# multiplex.net
KiCad netlist of a schematic drawn in EAGLE
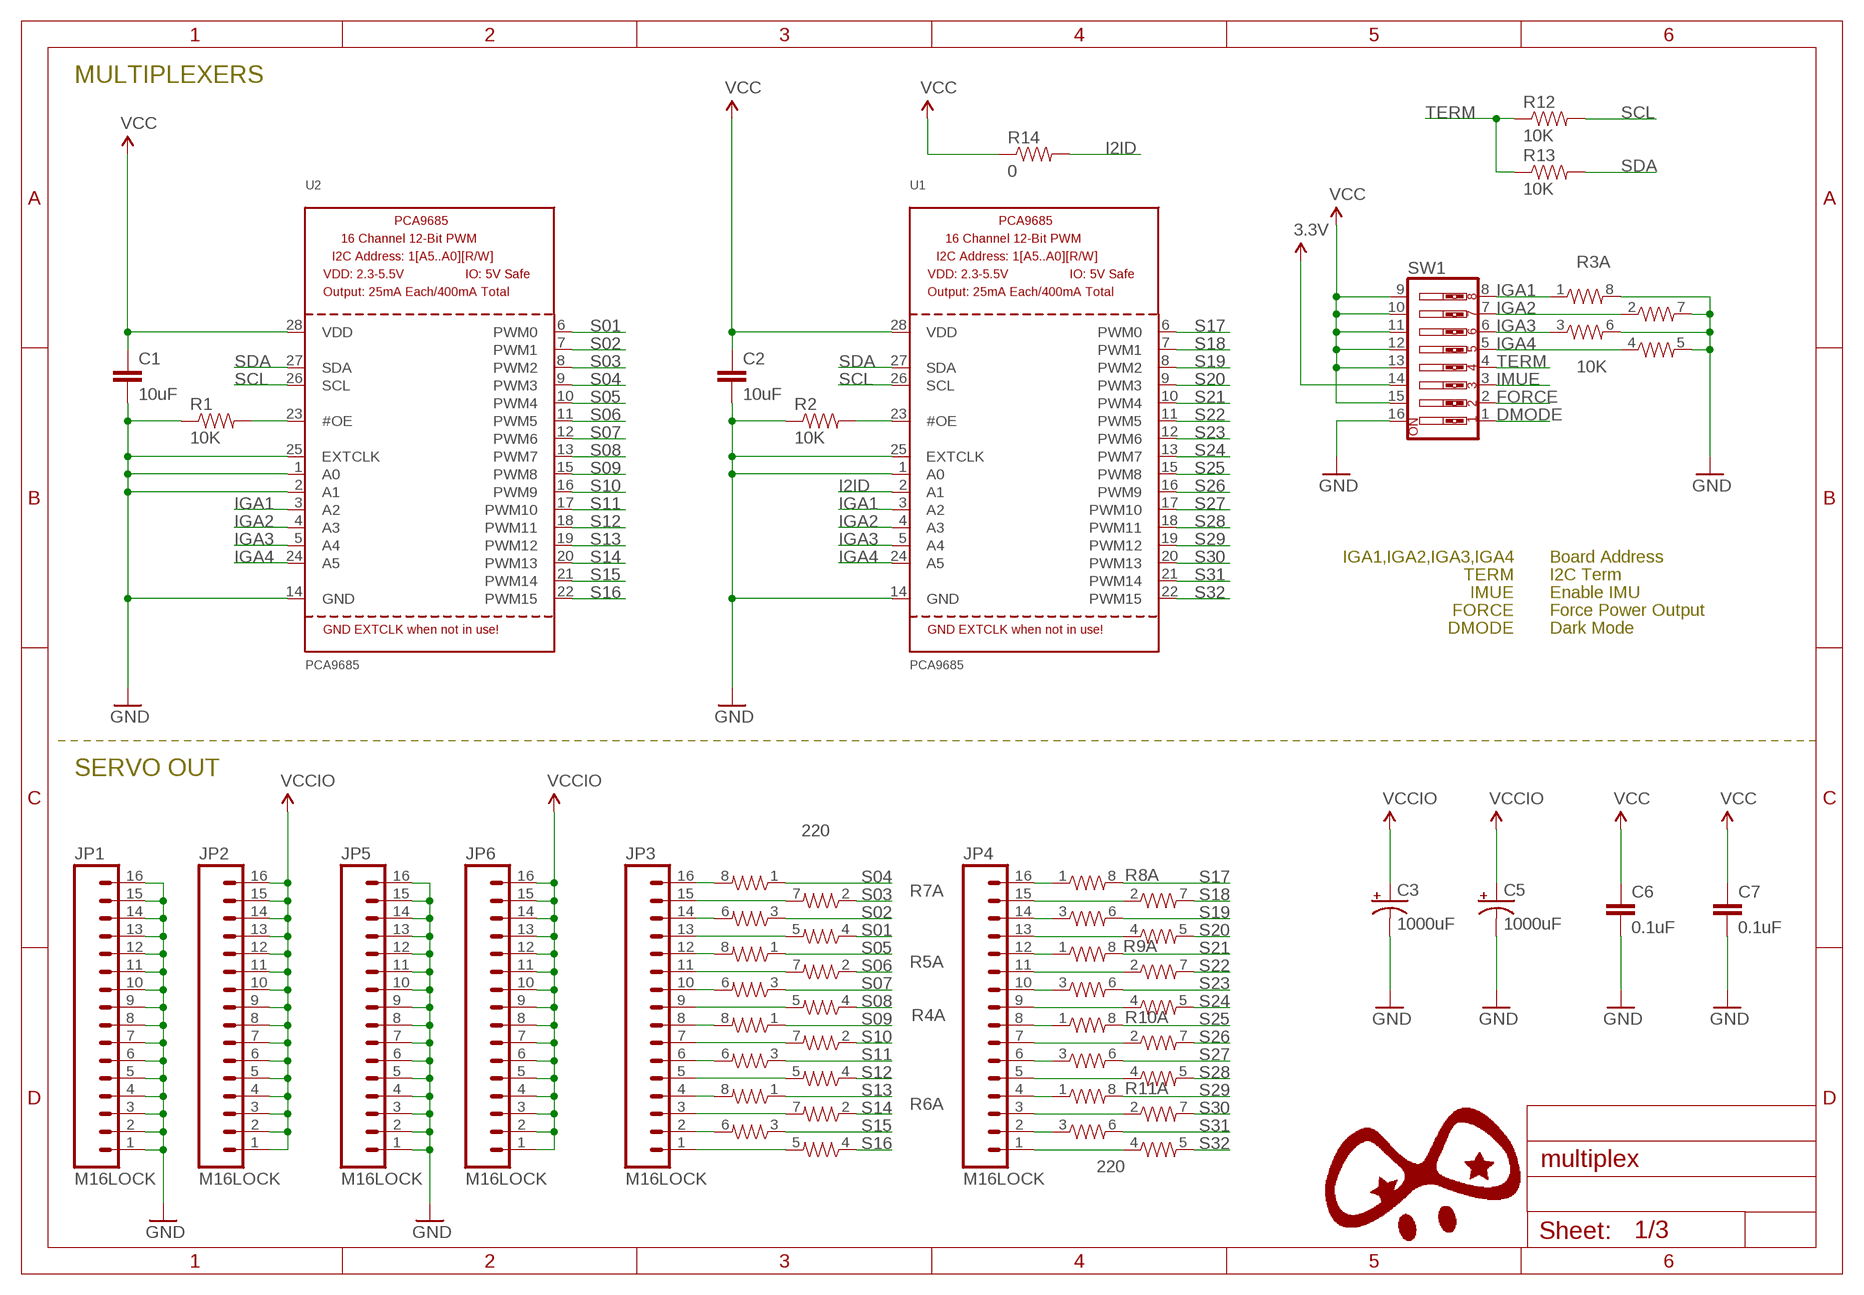
[diagram p0: schematic, sheet 1]
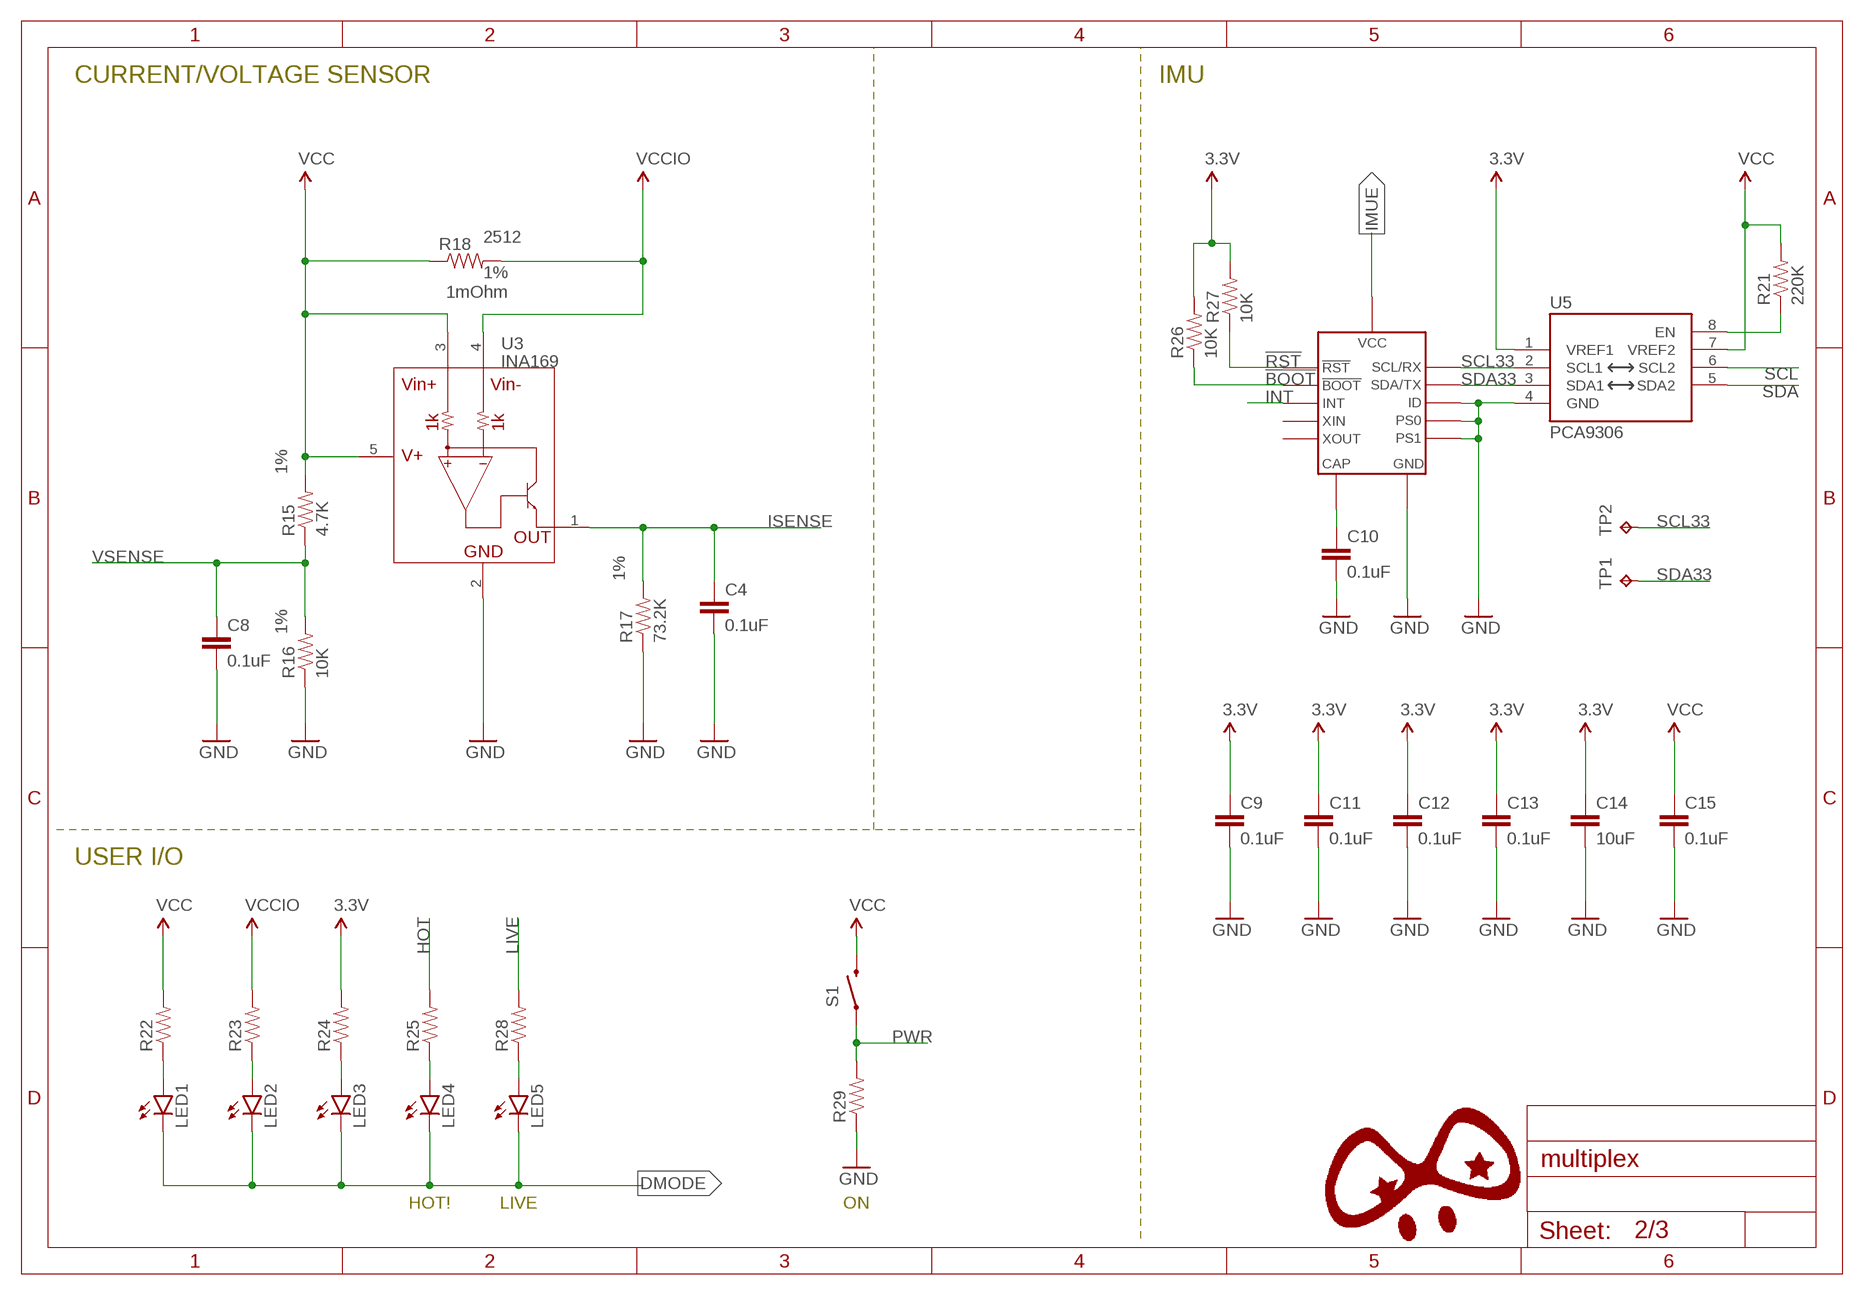
[diagram p1: schematic, sheet 2]
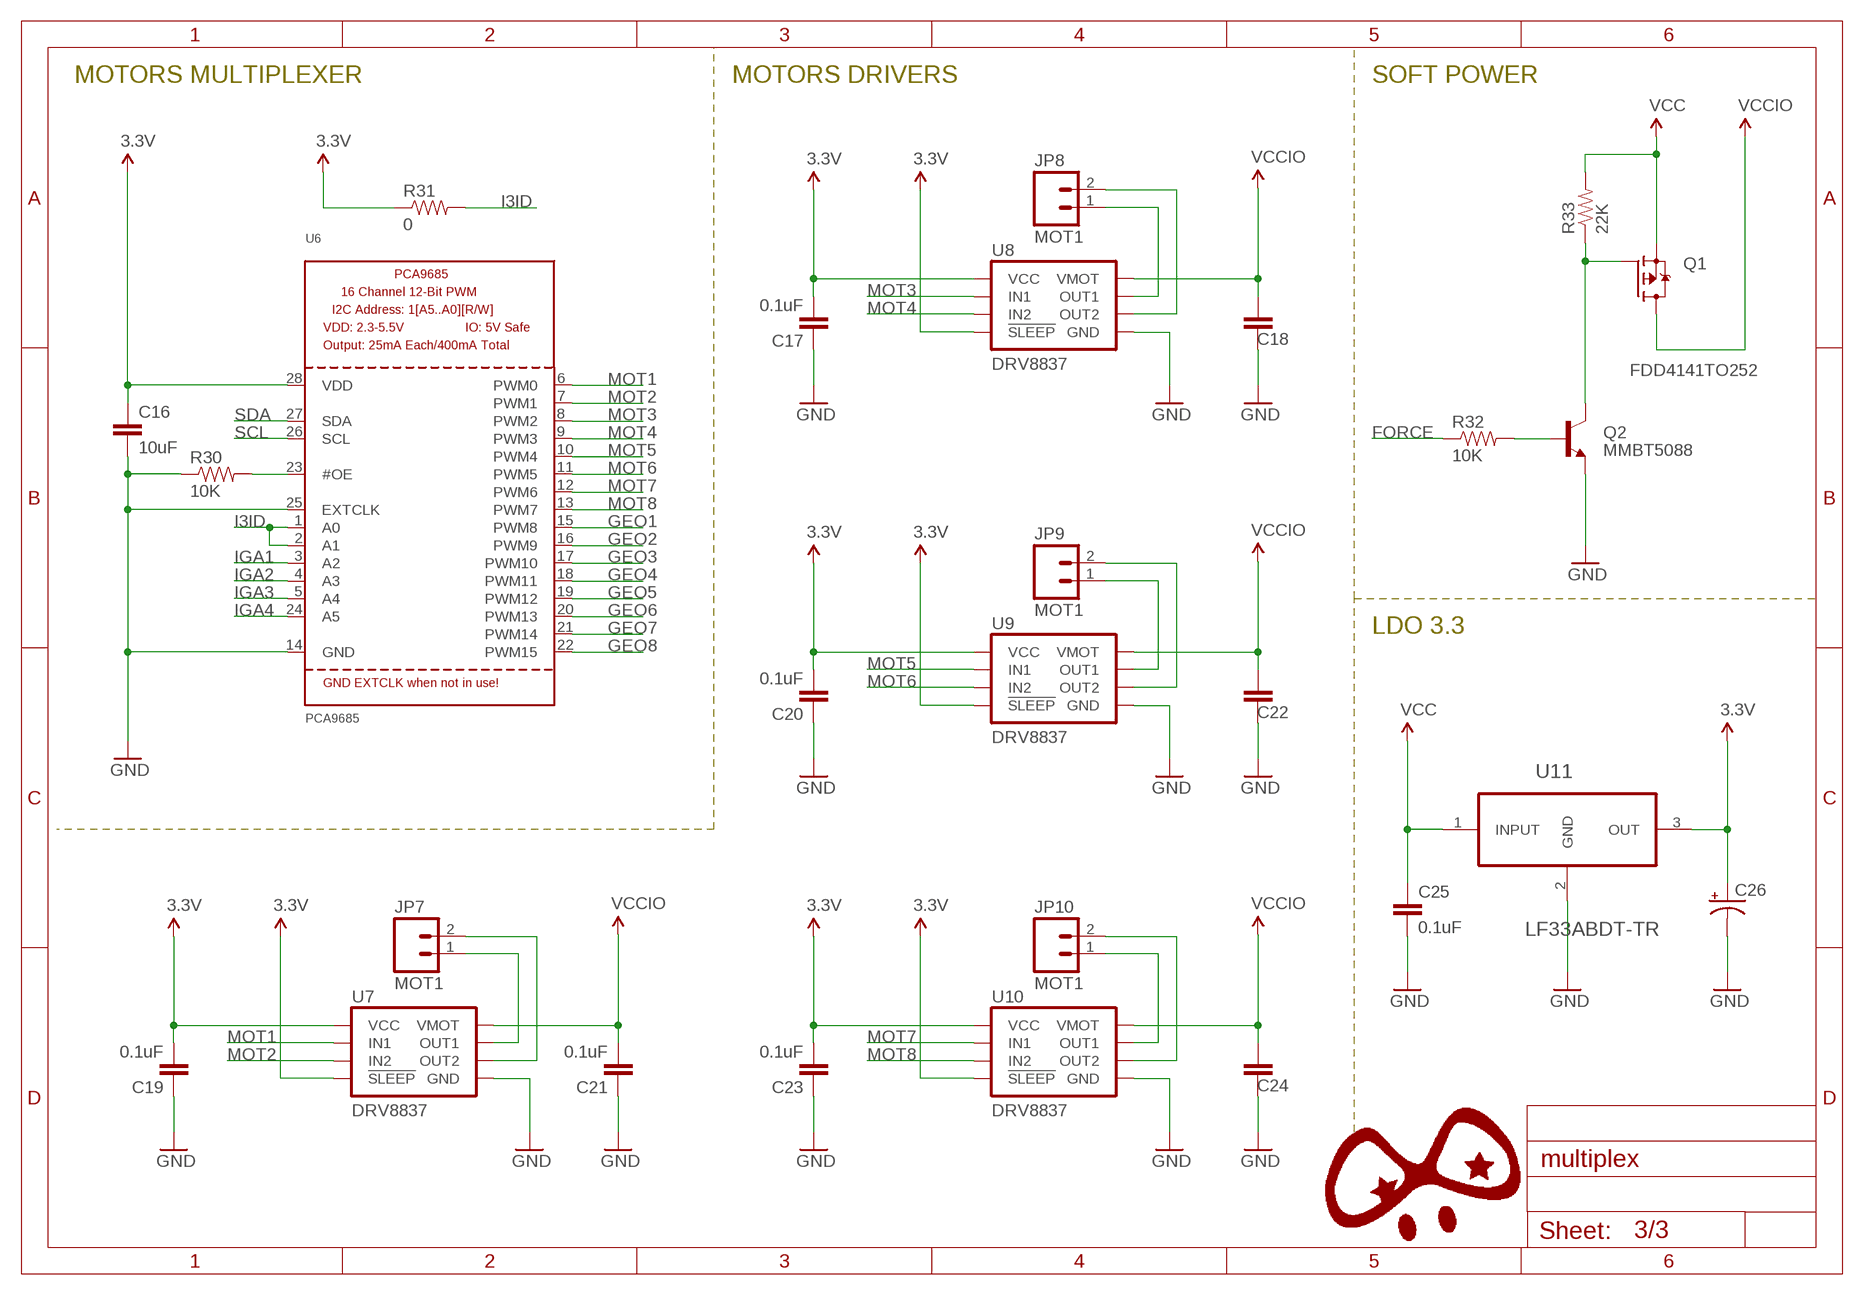
[diagram p2: schematic, sheet 3]

(export (version "E")
  (design (tool "Eeschema 10.0.6"))
  (components
    (comp (ref "C16")
      (value "10uF")
      (footprint "eagle-import:0603-CAP")
      (libsource (lib "eagle-import") (part "10UF-6.3V-20%(0603)"))
    )
    (comp (ref "C17")
      (value "0.1uF")
      (footprint "eagle-import:0603-CAP")
      (libsource (lib "eagle-import") (part "SparkFun-Passives_CAP0603-CAP"))
    )
    (comp (ref "C18")
      (value "0.1uF")
      (footprint "eagle-import:0603-CAP")
      (libsource (lib "eagle-import") (part "SparkFun-Passives_CAP0603-CAP"))
    )
    (comp (ref "C19")
      (value "0.1uF")
      (footprint "eagle-import:0603-CAP")
      (libsource (lib "eagle-import") (part "SparkFun-Passives_CAP0603-CAP"))
    )
    (comp (ref "C20")
      (value "0.1uF")
      (footprint "eagle-import:0603-CAP")
      (libsource (lib "eagle-import") (part "SparkFun-Passives_CAP0603-CAP"))
    )
    (comp (ref "C21")
      (value "0.1uF")
      (footprint "eagle-import:0603-CAP")
      (libsource (lib "eagle-import") (part "SparkFun-Passives_CAP0603-CAP"))
    )
    (comp (ref "C22")
      (value "0.1uF")
      (footprint "eagle-import:0603-CAP")
      (libsource (lib "eagle-import") (part "SparkFun-Passives_CAP0603-CAP"))
    )
    (comp (ref "C23")
      (value "0.1uF")
      (footprint "eagle-import:0603-CAP")
      (libsource (lib "eagle-import") (part "SparkFun-Passives_CAP0603-CAP"))
    )
    (comp (ref "C24")
      (value "0.1uF")
      (footprint "eagle-import:0603-CAP")
      (libsource (lib "eagle-import") (part "SparkFun-Passives_CAP0603-CAP"))
    )
    (comp (ref "C25")
      (value "0.1uF")
      (footprint "eagle-import:1210")
      (libsource (lib "eagle-import") (part "CAP1210"))
    )
    (comp (ref "C26")
      (value "CAP_POLD")
      (footprint "eagle-import:PANASONIC_D")
      (libsource (lib "eagle-import") (part "CAP_POLD"))
    )
    (comp (ref "JP7")
      (value "MOT1")
      (footprint "eagle-import:MOLEX-1X2")
      (libsource (lib "eagle-import") (part "M02POLAR"))
    )
    (comp (ref "JP8")
      (value "MOT1")
      (footprint "eagle-import:MOLEX-1X2")
      (libsource (lib "eagle-import") (part "M02POLAR"))
    )
    (comp (ref "JP9")
      (value "MOT1")
      (footprint "eagle-import:MOLEX-1X2")
      (libsource (lib "eagle-import") (part "M02POLAR"))
    )
    (comp (ref "JP10")
      (value "MOT1")
      (footprint "eagle-import:MOLEX-1X2")
      (libsource (lib "eagle-import") (part "M02POLAR"))
    )
    (comp (ref "Q1")
      (value "FDD4141TO252")
      (footprint "eagle-import:TO252")
      (libsource (lib "eagle-import") (part "FDD4141TO252"))
    )
    (comp (ref "Q2")
      (value "MMBT5088")
      (footprint "eagle-import:SOT23-3")
      (libsource (lib "eagle-import") (part "TRANSISTOR_NPNMMBT5088"))
    )
    (comp (ref "R30")
      (value "10K")
      (footprint "eagle-import:0603-RES")
      (libsource (lib "eagle-import") (part "RESISTOR0603"))
    )
    (comp (ref "R31")
      (value "0")
      (footprint "eagle-import:0603-RES")
      (libsource (lib "eagle-import") (part "RESISTOR0603"))
    )
    (comp (ref "R32")
      (value "10K")
      (footprint "eagle-import:0603-RES")
      (libsource (lib "eagle-import") (part "RESISTOR0603"))
    )
    (comp (ref "R33")
      (value "22K")
      (footprint "eagle-import:0603-RES")
      (libsource (lib "eagle-import") (part "RESISTOR0603"))
    )
    (comp (ref "U6")
      (value "PCA9685")
      (footprint "eagle-import:TSSOP28")
      (libsource (lib "eagle-import") (part "PCA9685"))
    )
    (comp (ref "U7")
      (value "DRV8837")
      (footprint "eagle-import:DSG")
      (libsource (lib "eagle-import") (part "DRV8837"))
    )
    (comp (ref "U8")
      (value "DRV8837")
      (footprint "eagle-import:DSG")
      (libsource (lib "eagle-import") (part "DRV8837"))
    )
    (comp (ref "U9")
      (value "DRV8837")
      (footprint "eagle-import:DSG")
      (libsource (lib "eagle-import") (part "DRV8837"))
    )
    (comp (ref "U10")
      (value "DRV8837")
      (footprint "eagle-import:DSG")
      (libsource (lib "eagle-import") (part "DRV8837"))
    )
    (comp (ref "U11")
      (value "LF33ABDT-TR")
      (footprint "eagle-import:TO228P972X240-3N")
      (libsource (lib "eagle-import") (part "LF33ABDT-TR"))
    )
    (comp (ref "C1")
      (value "10uF")
      (footprint "eagle-import:0603-CAP")
      (libsource (lib "eagle-import") (part "10UF-6.3V-20%(0603)"))
    )
    (comp (ref "C2")
      (value "10uF")
      (footprint "eagle-import:0603-CAP")
      (libsource (lib "eagle-import") (part "10UF-6.3V-20%(0603)"))
    )
    (comp (ref "C3")
      (value "1000uF")
      (footprint "eagle-import:PANASONIC_D")
      (libsource (lib "eagle-import") (part "CAP_POLD"))
    )
    (comp (ref "C5")
      (value "1000uF")
      (footprint "eagle-import:PANASONIC_D")
      (libsource (lib "eagle-import") (part "CAP_POLD"))
    )
    (comp (ref "C6")
      (value "0.1uF")
      (footprint "eagle-import:0603-CAP")
      (libsource (lib "eagle-import") (part "10UF-6.3V-20%(0603)"))
    )
    (comp (ref "C7")
      (value "0.1uF")
      (footprint "eagle-import:0603-CAP")
      (libsource (lib "eagle-import") (part "10UF-6.3V-20%(0603)"))
    )
    (comp (ref "JP1")
      (value "M16LOCK")
      (footprint "eagle-import:1X16_LOCK")
      (libsource (lib "eagle-import") (part "M16LOCK"))
    )
    (comp (ref "JP2")
      (value "M16LOCK")
      (footprint "eagle-import:1X16_LOCK")
      (libsource (lib "eagle-import") (part "M16LOCK"))
    )
    (comp (ref "JP3")
      (value "M16LOCK")
      (footprint "eagle-import:1X16_LOCK")
      (libsource (lib "eagle-import") (part "M16LOCK"))
    )
    (comp (ref "JP4")
      (value "M16LOCK")
      (footprint "eagle-import:1X16_LOCK")
      (libsource (lib "eagle-import") (part "M16LOCK"))
    )
    (comp (ref "JP5")
      (value "M16LOCK")
      (footprint "eagle-import:1X16_LOCK")
      (libsource (lib "eagle-import") (part "M16LOCK"))
    )
    (comp (ref "JP6")
      (value "M16LOCK")
      (footprint "eagle-import:1X16_LOCK")
      (libsource (lib "eagle-import") (part "M16LOCK"))
    )
    (comp (ref "R1")
      (value "10K")
      (footprint "eagle-import:0603-RES")
      (libsource (lib "eagle-import") (part "RESISTOR0603"))
    )
    (comp (ref "R2")
      (value "10K")
      (footprint "eagle-import:0603-RES")
      (libsource (lib "eagle-import") (part "RESISTOR0603"))
    )
    (comp (ref "R3")
      (value "10K")
      (footprint "eagle-import:0603-ARV")
      (libsource (lib "eagle-import") (part "RESISTOR-ARRAY0603-ARV"))
    )
    (comp (ref "R4")
      (value "220")
      (footprint "eagle-import:0603-ARV")
      (libsource (lib "eagle-import") (part "RESISTOR-ARRAY0603-ARV"))
    )
    (comp (ref "R5")
      (value "220")
      (footprint "eagle-import:0603-ARV")
      (libsource (lib "eagle-import") (part "RESISTOR-ARRAY0603-ARV"))
    )
    (comp (ref "R6")
      (value "220")
      (footprint "eagle-import:0603-ARV")
      (libsource (lib "eagle-import") (part "RESISTOR-ARRAY0603-ARV"))
    )
    (comp (ref "R7")
      (value "220")
      (footprint "eagle-import:0603-ARV")
      (libsource (lib "eagle-import") (part "RESISTOR-ARRAY0603-ARV"))
    )
    (comp (ref "R8")
      (value "220")
      (footprint "eagle-import:0603-ARV")
      (libsource (lib "eagle-import") (part "RESISTOR-ARRAY0603-ARV"))
    )
    (comp (ref "R9")
      (value "220")
      (footprint "eagle-import:0603-ARV")
      (libsource (lib "eagle-import") (part "RESISTOR-ARRAY0603-ARV"))
    )
    (comp (ref "R10")
      (value "220")
      (footprint "eagle-import:0603-ARV")
      (libsource (lib "eagle-import") (part "RESISTOR-ARRAY0603-ARV"))
    )
    (comp (ref "R11")
      (value "220")
      (footprint "eagle-import:0603-ARV")
      (libsource (lib "eagle-import") (part "RESISTOR-ARRAY0603-ARV"))
    )
    (comp (ref "R12")
      (value "10K")
      (footprint "eagle-import:0603-RES")
      (libsource (lib "eagle-import") (part "RESISTOR0603"))
    )
    (comp (ref "R13")
      (value "10K")
      (footprint "eagle-import:0603-RES")
      (libsource (lib "eagle-import") (part "RESISTOR0603"))
    )
    (comp (ref "R14")
      (value "0")
      (footprint "eagle-import:0603-RES")
      (libsource (lib "eagle-import") (part "RESISTOR0603"))
    )
    (comp (ref "SW1")
      (value "SW_DIP-8-SMT-HALFSIZE")
      (footprint "eagle-import:DIPSWITCH-08-50MIL")
      (libsource (lib "eagle-import") (part "SW_DIP-8-SMT-HALFSIZE"))
    )
    (comp (ref "U1")
      (value "PCA9685")
      (footprint "eagle-import:TSSOP28")
      (libsource (lib "eagle-import") (part "PCA9685"))
    )
    (comp (ref "U2")
      (value "PCA9685")
      (footprint "eagle-import:TSSOP28")
      (libsource (lib "eagle-import") (part "PCA9685"))
    )
    (comp (ref "C4")
      (value "0.1uF")
      (footprint "eagle-import:0603-CAP")
      (libsource (lib "eagle-import") (part "10UF-6.3V-20%(0603)"))
    )
    (comp (ref "C8")
      (value "0.1uF")
      (footprint "eagle-import:0603-CAP")
      (libsource (lib "eagle-import") (part "10UF-6.3V-20%(0603)"))
    )
    (comp (ref "C9")
      (value "0.1uF")
      (footprint "eagle-import:0603-CAP")
      (libsource (lib "eagle-import") (part "10UF-6.3V-20%(0603)"))
    )
    (comp (ref "C10")
      (value "0.1uF")
      (footprint "eagle-import:0603-CAP")
      (libsource (lib "eagle-import") (part "10UF-6.3V-20%(0603)"))
    )
    (comp (ref "C11")
      (value "0.1uF")
      (footprint "eagle-import:0603-CAP")
      (libsource (lib "eagle-import") (part "10UF-6.3V-20%(0603)"))
    )
    (comp (ref "C12")
      (value "0.1uF")
      (footprint "eagle-import:0603-CAP")
      (libsource (lib "eagle-import") (part "10UF-6.3V-20%(0603)"))
    )
    (comp (ref "C13")
      (value "0.1uF")
      (footprint "eagle-import:0603-CAP")
      (libsource (lib "eagle-import") (part "10UF-6.3V-20%(0603)"))
    )
    (comp (ref "C14")
      (value "10uF")
      (footprint "eagle-import:0603-CAP")
      (libsource (lib "eagle-import") (part "10UF-6.3V-20%(0603)"))
    )
    (comp (ref "C15")
      (value "0.1uF")
      (footprint "eagle-import:0603-CAP")
      (libsource (lib "eagle-import") (part "10UF-6.3V-20%(0603)"))
    )
    (comp (ref "LED1")
      (value "LED0603")
      (footprint "eagle-import:LED-0603")
      (libsource (lib "eagle-import") (part "LED0603"))
    )
    (comp (ref "LED2")
      (value "LED0603")
      (footprint "eagle-import:LED-0603")
      (libsource (lib "eagle-import") (part "LED0603"))
    )
    (comp (ref "LED3")
      (value "LED0603")
      (footprint "eagle-import:LED-0603")
      (libsource (lib "eagle-import") (part "LED0603"))
    )
    (comp (ref "LED4")
      (value "LED0603")
      (footprint "eagle-import:LED-0603")
      (libsource (lib "eagle-import") (part "LED0603"))
    )
    (comp (ref "LED5")
      (value "LED0603")
      (footprint "eagle-import:LED-0603")
      (libsource (lib "eagle-import") (part "LED0603"))
    )
    (comp (ref "R15")
      (value "4.7K")
      (footprint "eagle-import:0603-RES")
      (fields (field (name "TOL") "1%"))
      (libsource (lib "eagle-import") (part "RESISTOR0603"))
    )
    (comp (ref "R16")
      (value "10K")
      (footprint "eagle-import:0603-RES")
      (fields (field (name "TOL") "1%"))
      (libsource (lib "eagle-import") (part "RESISTOR0603"))
    )
    (comp (ref "R17")
      (value "73.2K")
      (footprint "eagle-import:0603-RES")
      (fields (field (name "TOL") "1%"))
      (libsource (lib "eagle-import") (part "RESISTOR0603"))
    )
    (comp (ref "R18")
      (value "1mOhm")
      (footprint "eagle-import:R2512")
      (fields (field (name "SIZE") "2512") (field (name "TOL") "1%"))
      (libsource (lib "eagle-import") (part "RESISTOR2512"))
    )
    (comp (ref "R21")
      (value "220K")
      (footprint "eagle-import:0603-RES")
      (libsource (lib "eagle-import") (part "RESISTOR0603-RES"))
    )
    (comp (ref "R22")
      (value "RESISTOR0603-RES")
      (footprint "eagle-import:0603-RES")
      (libsource (lib "eagle-import") (part "RESISTOR0603-RES"))
    )
    (comp (ref "R23")
      (value "RESISTOR0603-RES")
      (footprint "eagle-import:0603-RES")
      (libsource (lib "eagle-import") (part "RESISTOR0603-RES"))
    )
    (comp (ref "R24")
      (value "RESISTOR0603-RES")
      (footprint "eagle-import:0603-RES")
      (libsource (lib "eagle-import") (part "RESISTOR0603-RES"))
    )
    (comp (ref "R25")
      (value "RESISTOR0603-RES")
      (footprint "eagle-import:0603-RES")
      (libsource (lib "eagle-import") (part "RESISTOR0603-RES"))
    )
    (comp (ref "R26")
      (value "10K")
      (footprint "eagle-import:0603-RES")
      (libsource (lib "eagle-import") (part "RESISTOR0603"))
    )
    (comp (ref "R27")
      (value "10K")
      (footprint "eagle-import:0603-RES")
      (libsource (lib "eagle-import") (part "RESISTOR0603"))
    )
    (comp (ref "R28")
      (value "RESISTOR0603-RES")
      (footprint "eagle-import:0603-RES")
      (libsource (lib "eagle-import") (part "RESISTOR0603-RES"))
    )
    (comp (ref "R29")
      (value "RESISTOR0603-RES")
      (footprint "eagle-import:0603-RES")
      (libsource (lib "eagle-import") (part "RESISTOR0603-RES"))
    )
    (comp (ref "S1")
      (value "SWITCH-MOMENTARY-2SMD")
      (footprint "eagle-import:TACTILE-SWITCH-SMD")
      (libsource (lib "eagle-import") (part "SWITCH-MOMENTARY-2SMD"))
    )
    (comp (ref "TP1")
      (value "TPB1,27")
      (footprint "eagle-import:B1,27")
      (libsource (lib "eagle-import") (part "TPB1,27"))
    )
    (comp (ref "TP2")
      (value "TPB1,27")
      (footprint "eagle-import:B1,27")
      (libsource (lib "eagle-import") (part "TPB1,27"))
    )
    (comp (ref "U3")
      (value "INA169")
      (footprint "eagle-import:SOT23-5")
      (libsource (lib "eagle-import") (part "INA169"))
    )
    (comp (ref "U4")
      (value "BNO055")
      (footprint "eagle-import:BNO055")
      (libsource (lib "eagle-import") (part "BNO055"))
    )
    (comp (ref "U5")
      (value "PCA9306")
      (footprint "eagle-import:PCA9306DC-1_1")
      (libsource (lib "eagle-import") (part "PCA9306PCA9306DC-1{colon}1"))
    )
  )
  (nets
    (net (code "1") (name "3.3V") (class "Default")
      (node (ref "C11") (pin "1") (pinfunction "1_1") (pintype "passive"))
      (node (ref "C12") (pin "1") (pinfunction "1_1") (pintype "passive"))
      (node (ref "C13") (pin "1") (pinfunction "1_1") (pintype "passive"))
      (node (ref "C14") (pin "1") (pinfunction "1_1") (pintype "passive"))
      (node (ref "C16") (pin "1") (pinfunction "1_1") (pintype "passive"))
      (node (ref "C17") (pin "2") (pinfunction "2_2") (pintype "passive"))
      (node (ref "C19") (pin "2") (pinfunction "2_2") (pintype "passive"))
      (node (ref "C20") (pin "2") (pinfunction "2_2") (pintype "passive"))
      (node (ref "C23") (pin "2") (pinfunction "2_2") (pintype "passive"))
      (node (ref "C26") (pin "+") (pinfunction "+_+") (pintype "passive"))
      (node (ref "C9") (pin "1") (pinfunction "1_1") (pintype "passive"))
      (node (ref "R24") (pin "2") (pinfunction "2_2") (pintype "passive"))
      (node (ref "R26") (pin "2") (pinfunction "2_2") (pintype "passive"))
      (node (ref "R27") (pin "2") (pinfunction "2_2") (pintype "passive"))
      (node (ref "R31") (pin "1") (pinfunction "1_1") (pintype "passive"))
      (node (ref "SW1") (pin "14") (pinfunction "14_14") (pintype "passive"))
      (node (ref "U10") (pin "7") (pinfunction "~{SLEEP}_7") (pintype "bidirectional"))
      (node (ref "U10") (pin "8") (pinfunction "VCC_8") (pintype "bidirectional"))
      (node (ref "U11") (pin "3") (pinfunction "OUT_3") (pintype "output"))
      (node (ref "U5") (pin "1") (pinfunction "VREF1_1") (pintype "bidirectional"))
      (node (ref "U6") (pin "28") (pinfunction "VDD_28") (pintype "power_in"))
      (node (ref "U7") (pin "7") (pinfunction "~{SLEEP}_7") (pintype "bidirectional"))
      (node (ref "U7") (pin "8") (pinfunction "VCC_8") (pintype "bidirectional"))
      (node (ref "U8") (pin "7") (pinfunction "~{SLEEP}_7") (pintype "bidirectional"))
      (node (ref "U8") (pin "8") (pinfunction "VCC_8") (pintype "bidirectional"))
      (node (ref "U9") (pin "7") (pinfunction "~{SLEEP}_7") (pintype "bidirectional"))
      (node (ref "U9") (pin "8") (pinfunction "VCC_8") (pintype "bidirectional"))
    )
    (net (code "2") (name "DMODE") (class "Default")
      (node (ref "LED1") (pin "C") (pinfunction "C_C") (pintype "passive"))
      (node (ref "LED2") (pin "C") (pinfunction "C_C") (pintype "passive"))
      (node (ref "LED3") (pin "C") (pinfunction "C_C") (pintype "passive"))
      (node (ref "LED4") (pin "C") (pinfunction "C_C") (pintype "passive"))
      (node (ref "LED5") (pin "C") (pinfunction "C_C") (pintype "passive"))
      (node (ref "SW1") (pin "1") (pinfunction "1_1") (pintype "passive"))
    )
    (net (code "3") (name "FORCE") (class "Default")
      (node (ref "R32") (pin "1") (pinfunction "1_1") (pintype "passive"))
      (node (ref "SW1") (pin "2") (pinfunction "2_2") (pintype "passive"))
    )
    (net (code "4") (name "GEO1") (class "Default")
      (node (ref "U6") (pin "15") (pinfunction "PWM8_15") (pintype "output"))
    )
    (net (code "5") (name "GEO2") (class "Default")
      (node (ref "U6") (pin "16") (pinfunction "PWM9_16") (pintype "output"))
    )
    (net (code "6") (name "GEO3") (class "Default")
      (node (ref "U6") (pin "17") (pinfunction "PWM10_17") (pintype "output"))
    )
    (net (code "7") (name "GEO4") (class "Default")
      (node (ref "U6") (pin "18") (pinfunction "PWM11_18") (pintype "output"))
    )
    (net (code "8") (name "GEO5") (class "Default")
      (node (ref "U6") (pin "19") (pinfunction "PWM12_19") (pintype "output"))
    )
    (net (code "9") (name "GEO6") (class "Default")
      (node (ref "U6") (pin "20") (pinfunction "PWM13_20") (pintype "output"))
    )
    (net (code "10") (name "GEO7") (class "Default")
      (node (ref "U6") (pin "21") (pinfunction "PWM14_21") (pintype "output"))
    )
    (net (code "11") (name "GEO8") (class "Default")
      (node (ref "U6") (pin "22") (pinfunction "PWM15_22") (pintype "output"))
    )
    (net (code "12") (name "GND") (class "Default")
      (node (ref "C1") (pin "2") (pinfunction "2_2") (pintype "passive"))
      (node (ref "C10") (pin "2") (pinfunction "2_2") (pintype "passive"))
      (node (ref "C11") (pin "2") (pinfunction "2_2") (pintype "passive"))
      (node (ref "C12") (pin "2") (pinfunction "2_2") (pintype "passive"))
      (node (ref "C13") (pin "2") (pinfunction "2_2") (pintype "passive"))
      (node (ref "C14") (pin "2") (pinfunction "2_2") (pintype "passive"))
      (node (ref "C15") (pin "2") (pinfunction "2_2") (pintype "passive"))
      (node (ref "C16") (pin "2") (pinfunction "2_2") (pintype "passive"))
      (node (ref "C17") (pin "1") (pinfunction "1_1") (pintype "passive"))
      (node (ref "C18") (pin "1") (pinfunction "1_1") (pintype "passive"))
      (node (ref "C19") (pin "1") (pinfunction "1_1") (pintype "passive"))
      (node (ref "C2") (pin "2") (pinfunction "2_2") (pintype "passive"))
      (node (ref "C20") (pin "1") (pinfunction "1_1") (pintype "passive"))
      (node (ref "C21") (pin "1") (pinfunction "1_1") (pintype "passive"))
      (node (ref "C22") (pin "1") (pinfunction "1_1") (pintype "passive"))
      (node (ref "C23") (pin "1") (pinfunction "1_1") (pintype "passive"))
      (node (ref "C24") (pin "1") (pinfunction "1_1") (pintype "passive"))
      (node (ref "C25") (pin "2") (pinfunction "2_2") (pintype "passive"))
      (node (ref "C26") (pin "-") (pinfunction "-_-") (pintype "passive"))
      (node (ref "C3") (pin "-") (pinfunction "-_-") (pintype "passive"))
      (node (ref "C4") (pin "2") (pinfunction "2_2") (pintype "passive"))
      (node (ref "C5") (pin "-") (pinfunction "-_-") (pintype "passive"))
      (node (ref "C6") (pin "2") (pinfunction "2_2") (pintype "passive"))
      (node (ref "C7") (pin "2") (pinfunction "2_2") (pintype "passive"))
      (node (ref "C8") (pin "2") (pinfunction "2_2") (pintype "passive"))
      (node (ref "C9") (pin "2") (pinfunction "2_2") (pintype "passive"))
      (node (ref "JP1") (pin "1") (pinfunction "1_1") (pintype "passive"))
      (node (ref "JP1") (pin "10") (pinfunction "10_10") (pintype "passive"))
      (node (ref "JP1") (pin "11") (pinfunction "11_11") (pintype "passive"))
      (node (ref "JP1") (pin "12") (pinfunction "12_12") (pintype "passive"))
      (node (ref "JP1") (pin "13") (pinfunction "13_13") (pintype "passive"))
      (node (ref "JP1") (pin "14") (pinfunction "14_14") (pintype "passive"))
      (node (ref "JP1") (pin "15") (pinfunction "15_15") (pintype "passive"))
      (node (ref "JP1") (pin "16") (pinfunction "16_16") (pintype "passive"))
      (node (ref "JP1") (pin "2") (pinfunction "2_2") (pintype "passive"))
      (node (ref "JP1") (pin "3") (pinfunction "3_3") (pintype "passive"))
      (node (ref "JP1") (pin "4") (pinfunction "4_4") (pintype "passive"))
      (node (ref "JP1") (pin "5") (pinfunction "5_5") (pintype "passive"))
      (node (ref "JP1") (pin "6") (pinfunction "6_6") (pintype "passive"))
      (node (ref "JP1") (pin "7") (pinfunction "7_7") (pintype "passive"))
      (node (ref "JP1") (pin "8") (pinfunction "8_8") (pintype "passive"))
      (node (ref "JP1") (pin "9") (pinfunction "9_9") (pintype "passive"))
      (node (ref "JP5") (pin "1") (pinfunction "1_1") (pintype "passive"))
      (node (ref "JP5") (pin "10") (pinfunction "10_10") (pintype "passive"))
      (node (ref "JP5") (pin "11") (pinfunction "11_11") (pintype "passive"))
      (node (ref "JP5") (pin "12") (pinfunction "12_12") (pintype "passive"))
      (node (ref "JP5") (pin "13") (pinfunction "13_13") (pintype "passive"))
      (node (ref "JP5") (pin "14") (pinfunction "14_14") (pintype "passive"))
      (node (ref "JP5") (pin "15") (pinfunction "15_15") (pintype "passive"))
      (node (ref "JP5") (pin "16") (pinfunction "16_16") (pintype "passive"))
      (node (ref "JP5") (pin "2") (pinfunction "2_2") (pintype "passive"))
      (node (ref "JP5") (pin "3") (pinfunction "3_3") (pintype "passive"))
      (node (ref "JP5") (pin "4") (pinfunction "4_4") (pintype "passive"))
      (node (ref "JP5") (pin "5") (pinfunction "5_5") (pintype "passive"))
      (node (ref "JP5") (pin "6") (pinfunction "6_6") (pintype "passive"))
      (node (ref "JP5") (pin "7") (pinfunction "7_7") (pintype "passive"))
      (node (ref "JP5") (pin "8") (pinfunction "8_8") (pintype "passive"))
      (node (ref "JP5") (pin "9") (pinfunction "9_9") (pintype "passive"))
      (node (ref "Q2") (pin "2") (pinfunction "E_2") (pintype "passive"))
      (node (ref "R1") (pin "1") (pinfunction "1_1") (pintype "passive"))
      (node (ref "R16") (pin "1") (pinfunction "1_1") (pintype "passive"))
      (node (ref "R17") (pin "1") (pinfunction "1_1") (pintype "passive"))
      (node (ref "R2") (pin "1") (pinfunction "1_1") (pintype "passive"))
      (node (ref "R29") (pin "1") (pinfunction "1_1") (pintype "passive"))
      (node (ref "R3") (pin "5") (pinfunction "2_5") (pintype "passive"))
      (node (ref "R3") (pin "6") (pinfunction "2_6") (pintype "passive"))
      (node (ref "R3") (pin "7") (pinfunction "2_7") (pintype "passive"))
      (node (ref "R3") (pin "8") (pinfunction "2_8") (pintype "passive"))
      (node (ref "R30") (pin "1") (pinfunction "1_1") (pintype "passive"))
      (node (ref "SW1") (pin "16") (pinfunction "16_16") (pintype "passive"))
      (node (ref "U1") (pin "1") (pinfunction "A0_1") (pintype "bidirectional"))
      (node (ref "U1") (pin "14") (pinfunction "GND_14") (pintype "power_in"))
      (node (ref "U1") (pin "25") (pinfunction "EXTCLK_25") (pintype "input"))
      (node (ref "U10") (pin "4") (pinfunction "GND_4") (pintype "bidirectional"))
      (node (ref "U10") (pin "PAD") (pinfunction "GND_PAD") (pintype "bidirectional"))
      (node (ref "U11") (pin "2") (pinfunction "GND_2") (pintype "passive"))
      (node (ref "U2") (pin "1") (pinfunction "A0_1") (pintype "bidirectional"))
      (node (ref "U2") (pin "14") (pinfunction "GND_14") (pintype "power_in"))
      (node (ref "U2") (pin "2") (pinfunction "A1_2") (pintype "bidirectional"))
      (node (ref "U2") (pin "25") (pinfunction "EXTCLK_25") (pintype "input"))
      (node (ref "U3") (pin "2") (pinfunction "GND_2") (pintype "bidirectional"))
      (node (ref "U4") (pin "10") (pinfunction "GND_10") (pintype "power_in"))
      (node (ref "U4") (pin "15") (pinfunction "GND_15") (pintype "power_in"))
      (node (ref "U4") (pin "16") (pinfunction "GND_16") (pintype "power_in"))
      (node (ref "U4") (pin "17") (pinfunction "ID_17") (pintype "bidirectional"))
      (node (ref "U4") (pin "18") (pinfunction "GND_18") (pintype "power_in"))
      (node (ref "U4") (pin "2") (pinfunction "GND_2") (pintype "power_in"))
      (node (ref "U4") (pin "25") (pinfunction "GND_25") (pintype "power_in"))
      (node (ref "U4") (pin "5") (pinfunction "PS1_5") (pintype "bidirectional"))
      (node (ref "U4") (pin "6") (pinfunction "PS0_6") (pintype "bidirectional"))
      (node (ref "U5") (pin "4") (pinfunction "GND_4") (pintype "bidirectional"))
      (node (ref "U6") (pin "14") (pinfunction "GND_14") (pintype "power_in"))
      (node (ref "U6") (pin "25") (pinfunction "EXTCLK_25") (pintype "input"))
      (node (ref "U7") (pin "4") (pinfunction "GND_4") (pintype "bidirectional"))
      (node (ref "U7") (pin "PAD") (pinfunction "GND_PAD") (pintype "bidirectional"))
      (node (ref "U8") (pin "4") (pinfunction "GND_4") (pintype "bidirectional"))
      (node (ref "U8") (pin "PAD") (pinfunction "GND_PAD") (pintype "bidirectional"))
      (node (ref "U9") (pin "4") (pinfunction "GND_4") (pintype "bidirectional"))
      (node (ref "U9") (pin "PAD") (pinfunction "GND_PAD") (pintype "bidirectional"))
    )
    (net (code "13") (name "HOT") (class "Default")
      (node (ref "R25") (pin "2") (pinfunction "2_2") (pintype "passive"))
    )
    (net (code "14") (name "I2ID") (class "Default")
      (node (ref "R14") (pin "2") (pinfunction "2_2") (pintype "passive"))
      (node (ref "U1") (pin "2") (pinfunction "A1_2") (pintype "bidirectional"))
    )
    (net (code "15") (name "I3ID") (class "Default")
      (node (ref "R31") (pin "2") (pinfunction "2_2") (pintype "passive"))
      (node (ref "U6") (pin "1") (pinfunction "A0_1") (pintype "bidirectional"))
      (node (ref "U6") (pin "2") (pinfunction "A1_2") (pintype "bidirectional"))
    )
    (net (code "16") (name "IGA1") (class "Default")
      (node (ref "R3") (pin "1") (pinfunction "1_1") (pintype "passive"))
      (node (ref "SW1") (pin "8") (pinfunction "8_8") (pintype "passive"))
      (node (ref "U1") (pin "3") (pinfunction "A2_3") (pintype "bidirectional"))
      (node (ref "U2") (pin "3") (pinfunction "A2_3") (pintype "bidirectional"))
      (node (ref "U6") (pin "3") (pinfunction "A2_3") (pintype "bidirectional"))
    )
    (net (code "17") (name "IGA2") (class "Default")
      (node (ref "R3") (pin "2") (pinfunction "1_2") (pintype "passive"))
      (node (ref "SW1") (pin "7") (pinfunction "7_7") (pintype "passive"))
      (node (ref "U1") (pin "4") (pinfunction "A3_4") (pintype "bidirectional"))
      (node (ref "U2") (pin "4") (pinfunction "A3_4") (pintype "bidirectional"))
      (node (ref "U6") (pin "4") (pinfunction "A3_4") (pintype "bidirectional"))
    )
    (net (code "18") (name "IGA3") (class "Default")
      (node (ref "R3") (pin "3") (pinfunction "1_3") (pintype "passive"))
      (node (ref "SW1") (pin "6") (pinfunction "6_6") (pintype "passive"))
      (node (ref "U1") (pin "5") (pinfunction "A4_5") (pintype "bidirectional"))
      (node (ref "U2") (pin "5") (pinfunction "A4_5") (pintype "bidirectional"))
      (node (ref "U6") (pin "5") (pinfunction "A4_5") (pintype "bidirectional"))
    )
    (net (code "19") (name "IGA4") (class "Default")
      (node (ref "R3") (pin "4") (pinfunction "1_4") (pintype "passive"))
      (node (ref "SW1") (pin "5") (pinfunction "5_5") (pintype "passive"))
      (node (ref "U1") (pin "24") (pinfunction "A5_24") (pintype "bidirectional"))
      (node (ref "U2") (pin "24") (pinfunction "A5_24") (pintype "bidirectional"))
      (node (ref "U6") (pin "24") (pinfunction "A5_24") (pintype "bidirectional"))
    )
    (net (code "20") (name "IMUE") (class "Default")
      (node (ref "SW1") (pin "3") (pinfunction "3_3") (pintype "passive"))
      (node (ref "U4") (pin "28") (pinfunction "VCC_28") (pintype "bidirectional"))
      (node (ref "U4") (pin "3") (pinfunction "VCC_3") (pintype "bidirectional"))
    )
    (net (code "21") (name "INT") (class "Default")
      (node (ref "U4") (pin "14") (pinfunction "INT_14") (pintype "bidirectional"))
    )
    (net (code "22") (name "ISENSE") (class "Default")
      (node (ref "C4") (pin "1") (pinfunction "1_1") (pintype "passive"))
      (node (ref "R17") (pin "2") (pinfunction "2_2") (pintype "passive"))
      (node (ref "U3") (pin "1") (pinfunction "OUT_1") (pintype "bidirectional"))
    )
    (net (code "23") (name "LIVE") (class "Default")
      (node (ref "R28") (pin "2") (pinfunction "2_2") (pintype "passive"))
    )
    (net (code "24") (name "MOT1") (class "Default")
      (node (ref "U6") (pin "6") (pinfunction "PWM0_6") (pintype "output"))
      (node (ref "U7") (pin "6") (pinfunction "IN1_6") (pintype "bidirectional"))
    )
    (net (code "25") (name "MOT2") (class "Default")
      (node (ref "U6") (pin "7") (pinfunction "PWM1_7") (pintype "output"))
      (node (ref "U7") (pin "5") (pinfunction "IN2_5") (pintype "bidirectional"))
    )
    (net (code "26") (name "MOT3") (class "Default")
      (node (ref "U6") (pin "8") (pinfunction "PWM2_8") (pintype "output"))
      (node (ref "U8") (pin "6") (pinfunction "IN1_6") (pintype "bidirectional"))
    )
    (net (code "27") (name "MOT4") (class "Default")
      (node (ref "U6") (pin "9") (pinfunction "PWM3_9") (pintype "output"))
      (node (ref "U8") (pin "5") (pinfunction "IN2_5") (pintype "bidirectional"))
    )
    (net (code "28") (name "MOT5") (class "Default")
      (node (ref "U6") (pin "10") (pinfunction "PWM4_10") (pintype "output"))
      (node (ref "U9") (pin "6") (pinfunction "IN1_6") (pintype "bidirectional"))
    )
    (net (code "29") (name "MOT6") (class "Default")
      (node (ref "U6") (pin "11") (pinfunction "PWM5_11") (pintype "output"))
      (node (ref "U9") (pin "5") (pinfunction "IN2_5") (pintype "bidirectional"))
    )
    (net (code "30") (name "MOT7") (class "Default")
      (node (ref "U10") (pin "6") (pinfunction "IN1_6") (pintype "bidirectional"))
      (node (ref "U6") (pin "12") (pinfunction "PWM6_12") (pintype "output"))
    )
    (net (code "31") (name "MOT8") (class "Default")
      (node (ref "U10") (pin "5") (pinfunction "IN2_5") (pintype "bidirectional"))
      (node (ref "U6") (pin "13") (pinfunction "PWM7_13") (pintype "output"))
    )
    (net (code "32") (name "Net-(JP4-Pad4)") (class "Default")
      (node (ref "JP4") (pin "4") (pinfunction "4_4") (pintype "passive"))
      (node (ref "R11") (pin "1") (pinfunction "1_1") (pintype "passive"))
    )
    (net (code "33") (name "Net-(JP4-Pad8)") (class "Default")
      (node (ref "JP4") (pin "8") (pinfunction "8_8") (pintype "passive"))
      (node (ref "R10") (pin "1") (pinfunction "1_1") (pintype "passive"))
    )
    (net (code "34") (name "Net-(JP4-Pad12)") (class "Default")
      (node (ref "JP4") (pin "12") (pinfunction "12_12") (pintype "passive"))
      (node (ref "R9") (pin "1") (pinfunction "1_1") (pintype "passive"))
    )
    (net (code "35") (name "Net-(JP4-Pad16)") (class "Default")
      (node (ref "JP4") (pin "16") (pinfunction "16_16") (pintype "passive"))
      (node (ref "R8") (pin "1") (pinfunction "1_1") (pintype "passive"))
    )
    (net (code "36") (name "Net-(LED1-PadA)") (class "Default")
      (node (ref "LED1") (pin "A") (pinfunction "A_A") (pintype "passive"))
      (node (ref "R22") (pin "1") (pinfunction "1_1") (pintype "passive"))
    )
    (net (code "37") (name "Net-(LED2-PadA)") (class "Default")
      (node (ref "LED2") (pin "A") (pinfunction "A_A") (pintype "passive"))
      (node (ref "R23") (pin "1") (pinfunction "1_1") (pintype "passive"))
    )
    (net (code "38") (name "Net-(LED3-PadA)") (class "Default")
      (node (ref "LED3") (pin "A") (pinfunction "A_A") (pintype "passive"))
      (node (ref "R24") (pin "1") (pinfunction "1_1") (pintype "passive"))
    )
    (net (code "39") (name "Net-(LED4-PadA)") (class "Default")
      (node (ref "LED4") (pin "A") (pinfunction "A_A") (pintype "passive"))
      (node (ref "R25") (pin "1") (pinfunction "1_1") (pintype "passive"))
    )
    (net (code "40") (name "Net-(LED5-PadA)") (class "Default")
      (node (ref "LED5") (pin "A") (pinfunction "A_A") (pintype "passive"))
      (node (ref "R28") (pin "1") (pinfunction "1_1") (pintype "passive"))
    )
    (net (code "41") (name "Net-(Q1-G)") (class "Default")
      (node (ref "Q1") (pin "1") (pinfunction "G_1") (pintype "passive"))
      (node (ref "Q2") (pin "3") (pinfunction "C_3") (pintype "passive"))
      (node (ref "R33") (pin "1") (pinfunction "1_1") (pintype "passive"))
    )
    (net (code "42") (name "Net-(Q2-B)") (class "Default")
      (node (ref "Q2") (pin "1") (pinfunction "B_1") (pintype "passive"))
      (node (ref "R32") (pin "2") (pinfunction "2_2") (pintype "passive"))
    )
    (net (code "43") (name "Net-(R4A-2)") (class "Default")
      (node (ref "JP3") (pin "8") (pinfunction "8_8") (pintype "passive"))
      (node (ref "R4") (pin "8") (pinfunction "2_8") (pintype "passive"))
    )
    (net (code "44") (name "Net-(R4B-2)") (class "Default")
      (node (ref "JP3") (pin "7") (pinfunction "7_7") (pintype "passive"))
      (node (ref "R4") (pin "7") (pinfunction "2_7") (pintype "passive"))
    )
    (net (code "45") (name "Net-(R4C-2)") (class "Default")
      (node (ref "JP3") (pin "5") (pinfunction "5_5") (pintype "passive"))
      (node (ref "R4") (pin "5") (pinfunction "2_5") (pintype "passive"))
    )
    (net (code "46") (name "Net-(R4D-2)") (class "Default")
      (node (ref "JP3") (pin "6") (pinfunction "6_6") (pintype "passive"))
      (node (ref "R4") (pin "6") (pinfunction "2_6") (pintype "passive"))
    )
    (net (code "47") (name "Net-(R5A-2)") (class "Default")
      (node (ref "JP3") (pin "12") (pinfunction "12_12") (pintype "passive"))
      (node (ref "R5") (pin "8") (pinfunction "2_8") (pintype "passive"))
    )
    (net (code "48") (name "Net-(R5B-2)") (class "Default")
      (node (ref "JP3") (pin "11") (pinfunction "11_11") (pintype "passive"))
      (node (ref "R5") (pin "7") (pinfunction "2_7") (pintype "passive"))
    )
    (net (code "49") (name "Net-(R5C-2)") (class "Default")
      (node (ref "JP3") (pin "9") (pinfunction "9_9") (pintype "passive"))
      (node (ref "R5") (pin "5") (pinfunction "2_5") (pintype "passive"))
    )
    (net (code "50") (name "Net-(R5D-2)") (class "Default")
      (node (ref "JP3") (pin "10") (pinfunction "10_10") (pintype "passive"))
      (node (ref "R5") (pin "6") (pinfunction "2_6") (pintype "passive"))
    )
    (net (code "51") (name "Net-(R6A-2)") (class "Default")
      (node (ref "JP3") (pin "4") (pinfunction "4_4") (pintype "passive"))
      (node (ref "R6") (pin "8") (pinfunction "2_8") (pintype "passive"))
    )
    (net (code "52") (name "Net-(R6B-2)") (class "Default")
      (node (ref "JP3") (pin "3") (pinfunction "3_3") (pintype "passive"))
      (node (ref "R6") (pin "7") (pinfunction "2_7") (pintype "passive"))
    )
    (net (code "53") (name "Net-(R6C-2)") (class "Default")
      (node (ref "JP3") (pin "1") (pinfunction "1_1") (pintype "passive"))
      (node (ref "R6") (pin "5") (pinfunction "2_5") (pintype "passive"))
    )
    (net (code "54") (name "Net-(R6D-2)") (class "Default")
      (node (ref "JP3") (pin "2") (pinfunction "2_2") (pintype "passive"))
      (node (ref "R6") (pin "6") (pinfunction "2_6") (pintype "passive"))
    )
    (net (code "55") (name "Net-(R7A-2)") (class "Default")
      (node (ref "JP3") (pin "16") (pinfunction "16_16") (pintype "passive"))
      (node (ref "R7") (pin "8") (pinfunction "2_8") (pintype "passive"))
    )
    (net (code "56") (name "Net-(R7B-2)") (class "Default")
      (node (ref "JP3") (pin "15") (pinfunction "15_15") (pintype "passive"))
      (node (ref "R7") (pin "7") (pinfunction "2_7") (pintype "passive"))
    )
    (net (code "57") (name "Net-(R7C-2)") (class "Default")
      (node (ref "JP3") (pin "13") (pinfunction "13_13") (pintype "passive"))
      (node (ref "R7") (pin "5") (pinfunction "2_5") (pintype "passive"))
    )
    (net (code "58") (name "Net-(R7D-2)") (class "Default")
      (node (ref "JP3") (pin "14") (pinfunction "14_14") (pintype "passive"))
      (node (ref "R7") (pin "6") (pinfunction "2_6") (pintype "passive"))
    )
    (net (code "59") (name "Net-(R8B-1)") (class "Default")
      (node (ref "JP4") (pin "15") (pinfunction "15_15") (pintype "passive"))
      (node (ref "R8") (pin "2") (pinfunction "1_2") (pintype "passive"))
    )
    (net (code "60") (name "Net-(R8C-1)") (class "Default")
      (node (ref "JP4") (pin "13") (pinfunction "13_13") (pintype "passive"))
      (node (ref "R8") (pin "4") (pinfunction "1_4") (pintype "passive"))
    )
    (net (code "61") (name "Net-(R8D-1)") (class "Default")
      (node (ref "JP4") (pin "14") (pinfunction "14_14") (pintype "passive"))
      (node (ref "R8") (pin "3") (pinfunction "1_3") (pintype "passive"))
    )
    (net (code "62") (name "Net-(R9B-1)") (class "Default")
      (node (ref "JP4") (pin "11") (pinfunction "11_11") (pintype "passive"))
      (node (ref "R9") (pin "2") (pinfunction "1_2") (pintype "passive"))
    )
    (net (code "63") (name "Net-(R9C-1)") (class "Default")
      (node (ref "JP4") (pin "9") (pinfunction "9_9") (pintype "passive"))
      (node (ref "R9") (pin "4") (pinfunction "1_4") (pintype "passive"))
    )
    (net (code "64") (name "Net-(R9D-1)") (class "Default")
      (node (ref "JP4") (pin "10") (pinfunction "10_10") (pintype "passive"))
      (node (ref "R9") (pin "3") (pinfunction "1_3") (pintype "passive"))
    )
    (net (code "65") (name "Net-(R10B-1)") (class "Default")
      (node (ref "JP4") (pin "7") (pinfunction "7_7") (pintype "passive"))
      (node (ref "R10") (pin "2") (pinfunction "1_2") (pintype "passive"))
    )
    (net (code "66") (name "Net-(R10C-1)") (class "Default")
      (node (ref "JP4") (pin "5") (pinfunction "5_5") (pintype "passive"))
      (node (ref "R10") (pin "4") (pinfunction "1_4") (pintype "passive"))
    )
    (net (code "67") (name "Net-(R10D-1)") (class "Default")
      (node (ref "JP4") (pin "6") (pinfunction "6_6") (pintype "passive"))
      (node (ref "R10") (pin "3") (pinfunction "1_3") (pintype "passive"))
    )
    (net (code "68") (name "Net-(R11B-1)") (class "Default")
      (node (ref "JP4") (pin "3") (pinfunction "3_3") (pintype "passive"))
      (node (ref "R11") (pin "2") (pinfunction "1_2") (pintype "passive"))
    )
    (net (code "69") (name "Net-(R11C-1)") (class "Default")
      (node (ref "JP4") (pin "1") (pinfunction "1_1") (pintype "passive"))
      (node (ref "R11") (pin "4") (pinfunction "1_4") (pintype "passive"))
    )
    (net (code "70") (name "Net-(R11D-1)") (class "Default")
      (node (ref "JP4") (pin "2") (pinfunction "2_2") (pintype "passive"))
      (node (ref "R11") (pin "3") (pinfunction "1_3") (pintype "passive"))
    )
    (net (code "71") (name "Net-(U1-#OE)") (class "Default")
      (node (ref "R2") (pin "2") (pinfunction "2_2") (pintype "passive"))
      (node (ref "U1") (pin "23") (pinfunction "#OE_23") (pintype "input"))
    )
    (net (code "72") (name "Net-(U2-#OE)") (class "Default")
      (node (ref "R1") (pin "2") (pinfunction "2_2") (pintype "passive"))
      (node (ref "U2") (pin "23") (pinfunction "#OE_23") (pintype "input"))
    )
    (net (code "73") (name "Net-(U4-CAP)") (class "Default")
      (node (ref "C10") (pin "1") (pinfunction "1_1") (pintype "passive"))
      (node (ref "U4") (pin "9") (pinfunction "CAP_9") (pintype "bidirectional"))
    )
    (net (code "74") (name "Net-(U5-EN)") (class "Default")
      (node (ref "R21") (pin "1") (pinfunction "1_1") (pintype "passive"))
      (node (ref "U5") (pin "8") (pinfunction "EN_8") (pintype "bidirectional"))
    )
    (net (code "75") (name "Net-(U6-#OE)") (class "Default")
      (node (ref "R30") (pin "2") (pinfunction "2_2") (pintype "passive"))
      (node (ref "U6") (pin "23") (pinfunction "#OE_23") (pintype "input"))
    )
    (net (code "76") (name "Net-(U7-OUT1)") (class "Default")
      (node (ref "JP7") (pin "1") (pinfunction "1_1") (pintype "passive"))
      (node (ref "U7") (pin "2") (pinfunction "OUT1_2") (pintype "bidirectional"))
    )
    (net (code "77") (name "Net-(U7-OUT2)") (class "Default")
      (node (ref "JP7") (pin "2") (pinfunction "2_2") (pintype "passive"))
      (node (ref "U7") (pin "3") (pinfunction "OUT2_3") (pintype "bidirectional"))
    )
    (net (code "78") (name "Net-(U8-OUT1)") (class "Default")
      (node (ref "JP8") (pin "1") (pinfunction "1_1") (pintype "passive"))
      (node (ref "U8") (pin "2") (pinfunction "OUT1_2") (pintype "bidirectional"))
    )
    (net (code "79") (name "Net-(U8-OUT2)") (class "Default")
      (node (ref "JP8") (pin "2") (pinfunction "2_2") (pintype "passive"))
      (node (ref "U8") (pin "3") (pinfunction "OUT2_3") (pintype "bidirectional"))
    )
    (net (code "80") (name "Net-(U9-OUT1)") (class "Default")
      (node (ref "JP9") (pin "1") (pinfunction "1_1") (pintype "passive"))
      (node (ref "U9") (pin "2") (pinfunction "OUT1_2") (pintype "bidirectional"))
    )
    (net (code "81") (name "Net-(U9-OUT2)") (class "Default")
      (node (ref "JP9") (pin "2") (pinfunction "2_2") (pintype "passive"))
      (node (ref "U9") (pin "3") (pinfunction "OUT2_3") (pintype "bidirectional"))
    )
    (net (code "82") (name "Net-(U10-OUT1)") (class "Default")
      (node (ref "JP10") (pin "1") (pinfunction "1_1") (pintype "passive"))
      (node (ref "U10") (pin "2") (pinfunction "OUT1_2") (pintype "bidirectional"))
    )
    (net (code "83") (name "Net-(U10-OUT2)") (class "Default")
      (node (ref "JP10") (pin "2") (pinfunction "2_2") (pintype "passive"))
      (node (ref "U10") (pin "3") (pinfunction "OUT2_3") (pintype "bidirectional"))
    )
    (net (code "84") (name "PWR") (class "Default")
      (node (ref "R29") (pin "2") (pinfunction "2_2") (pintype "passive"))
      (node (ref "S1") (pin "1") (pinfunction "1_1") (pintype "passive"))
    )
    (net (code "85") (name "S01") (class "Default")
      (node (ref "R7") (pin "4") (pinfunction "1_4") (pintype "passive"))
      (node (ref "U2") (pin "6") (pinfunction "PWM0_6") (pintype "output"))
    )
    (net (code "86") (name "S02") (class "Default")
      (node (ref "R7") (pin "3") (pinfunction "1_3") (pintype "passive"))
      (node (ref "U2") (pin "7") (pinfunction "PWM1_7") (pintype "output"))
    )
    (net (code "87") (name "S03") (class "Default")
      (node (ref "R7") (pin "2") (pinfunction "1_2") (pintype "passive"))
      (node (ref "U2") (pin "8") (pinfunction "PWM2_8") (pintype "output"))
    )
    (net (code "88") (name "S04") (class "Default")
      (node (ref "R7") (pin "1") (pinfunction "1_1") (pintype "passive"))
      (node (ref "U2") (pin "9") (pinfunction "PWM3_9") (pintype "output"))
    )
    (net (code "89") (name "S05") (class "Default")
      (node (ref "R5") (pin "1") (pinfunction "1_1") (pintype "passive"))
      (node (ref "U2") (pin "10") (pinfunction "PWM4_10") (pintype "output"))
    )
    (net (code "90") (name "S06") (class "Default")
      (node (ref "R5") (pin "2") (pinfunction "1_2") (pintype "passive"))
      (node (ref "U2") (pin "11") (pinfunction "PWM5_11") (pintype "output"))
    )
    (net (code "91") (name "S07") (class "Default")
      (node (ref "R5") (pin "3") (pinfunction "1_3") (pintype "passive"))
      (node (ref "U2") (pin "12") (pinfunction "PWM6_12") (pintype "output"))
    )
    (net (code "92") (name "S08") (class "Default")
      (node (ref "R5") (pin "4") (pinfunction "1_4") (pintype "passive"))
      (node (ref "U2") (pin "13") (pinfunction "PWM7_13") (pintype "output"))
    )
    (net (code "93") (name "S09") (class "Default")
      (node (ref "R4") (pin "1") (pinfunction "1_1") (pintype "passive"))
      (node (ref "U2") (pin "15") (pinfunction "PWM8_15") (pintype "output"))
    )
    (net (code "94") (name "S10") (class "Default")
      (node (ref "R4") (pin "2") (pinfunction "1_2") (pintype "passive"))
      (node (ref "U2") (pin "16") (pinfunction "PWM9_16") (pintype "output"))
    )
    (net (code "95") (name "S11") (class "Default")
      (node (ref "R4") (pin "3") (pinfunction "1_3") (pintype "passive"))
      (node (ref "U2") (pin "17") (pinfunction "PWM10_17") (pintype "output"))
    )
    (net (code "96") (name "S12") (class "Default")
      (node (ref "R4") (pin "4") (pinfunction "1_4") (pintype "passive"))
      (node (ref "U2") (pin "18") (pinfunction "PWM11_18") (pintype "output"))
    )
    (net (code "97") (name "S13") (class "Default")
      (node (ref "R6") (pin "1") (pinfunction "1_1") (pintype "passive"))
      (node (ref "U2") (pin "19") (pinfunction "PWM12_19") (pintype "output"))
    )
    (net (code "98") (name "S14") (class "Default")
      (node (ref "R6") (pin "2") (pinfunction "1_2") (pintype "passive"))
      (node (ref "U2") (pin "20") (pinfunction "PWM13_20") (pintype "output"))
    )
    (net (code "99") (name "S15") (class "Default")
      (node (ref "R6") (pin "3") (pinfunction "1_3") (pintype "passive"))
      (node (ref "U2") (pin "21") (pinfunction "PWM14_21") (pintype "output"))
    )
    (net (code "100") (name "S16") (class "Default")
      (node (ref "R6") (pin "4") (pinfunction "1_4") (pintype "passive"))
      (node (ref "U2") (pin "22") (pinfunction "PWM15_22") (pintype "output"))
    )
    (net (code "101") (name "S17") (class "Default")
      (node (ref "R8") (pin "8") (pinfunction "2_8") (pintype "passive"))
      (node (ref "U1") (pin "6") (pinfunction "PWM0_6") (pintype "output"))
    )
    (net (code "102") (name "S18") (class "Default")
      (node (ref "R8") (pin "7") (pinfunction "2_7") (pintype "passive"))
      (node (ref "U1") (pin "7") (pinfunction "PWM1_7") (pintype "output"))
    )
    (net (code "103") (name "S19") (class "Default")
      (node (ref "R8") (pin "6") (pinfunction "2_6") (pintype "passive"))
      (node (ref "U1") (pin "8") (pinfunction "PWM2_8") (pintype "output"))
    )
    (net (code "104") (name "S20") (class "Default")
      (node (ref "R8") (pin "5") (pinfunction "2_5") (pintype "passive"))
      (node (ref "U1") (pin "9") (pinfunction "PWM3_9") (pintype "output"))
    )
    (net (code "105") (name "S21") (class "Default")
      (node (ref "R9") (pin "8") (pinfunction "2_8") (pintype "passive"))
      (node (ref "U1") (pin "10") (pinfunction "PWM4_10") (pintype "output"))
    )
    (net (code "106") (name "S22") (class "Default")
      (node (ref "R9") (pin "7") (pinfunction "2_7") (pintype "passive"))
      (node (ref "U1") (pin "11") (pinfunction "PWM5_11") (pintype "output"))
    )
    (net (code "107") (name "S23") (class "Default")
      (node (ref "R9") (pin "6") (pinfunction "2_6") (pintype "passive"))
      (node (ref "U1") (pin "12") (pinfunction "PWM6_12") (pintype "output"))
    )
    (net (code "108") (name "S24") (class "Default")
      (node (ref "R9") (pin "5") (pinfunction "2_5") (pintype "passive"))
      (node (ref "U1") (pin "13") (pinfunction "PWM7_13") (pintype "output"))
    )
    (net (code "109") (name "S25") (class "Default")
      (node (ref "R10") (pin "8") (pinfunction "2_8") (pintype "passive"))
      (node (ref "U1") (pin "15") (pinfunction "PWM8_15") (pintype "output"))
    )
    (net (code "110") (name "S26") (class "Default")
      (node (ref "R10") (pin "7") (pinfunction "2_7") (pintype "passive"))
      (node (ref "U1") (pin "16") (pinfunction "PWM9_16") (pintype "output"))
    )
    (net (code "111") (name "S27") (class "Default")
      (node (ref "R10") (pin "6") (pinfunction "2_6") (pintype "passive"))
      (node (ref "U1") (pin "17") (pinfunction "PWM10_17") (pintype "output"))
    )
    (net (code "112") (name "S28") (class "Default")
      (node (ref "R10") (pin "5") (pinfunction "2_5") (pintype "passive"))
      (node (ref "U1") (pin "18") (pinfunction "PWM11_18") (pintype "output"))
    )
    (net (code "113") (name "S29") (class "Default")
      (node (ref "R11") (pin "8") (pinfunction "2_8") (pintype "passive"))
      (node (ref "U1") (pin "19") (pinfunction "PWM12_19") (pintype "output"))
    )
    (net (code "114") (name "S30") (class "Default")
      (node (ref "R11") (pin "7") (pinfunction "2_7") (pintype "passive"))
      (node (ref "U1") (pin "20") (pinfunction "PWM13_20") (pintype "output"))
    )
    (net (code "115") (name "S31") (class "Default")
      (node (ref "R11") (pin "6") (pinfunction "2_6") (pintype "passive"))
      (node (ref "U1") (pin "21") (pinfunction "PWM14_21") (pintype "output"))
    )
    (net (code "116") (name "S32") (class "Default")
      (node (ref "R11") (pin "5") (pinfunction "2_5") (pintype "passive"))
      (node (ref "U1") (pin "22") (pinfunction "PWM15_22") (pintype "output"))
    )
    (net (code "117") (name "SCL") (class "Default")
      (node (ref "R12") (pin "2") (pinfunction "2_2") (pintype "passive"))
      (node (ref "U1") (pin "26") (pinfunction "SCL_26") (pintype "bidirectional"))
      (node (ref "U2") (pin "26") (pinfunction "SCL_26") (pintype "bidirectional"))
      (node (ref "U5") (pin "6") (pinfunction "SCL2_6") (pintype "bidirectional"))
      (node (ref "U6") (pin "26") (pinfunction "SCL_26") (pintype "bidirectional"))
    )
    (net (code "118") (name "SCL33") (class "Default")
      (node (ref "TP2") (pin "TP") (pinfunction "TP_TP") (pintype "input"))
      (node (ref "U4") (pin "19") (pinfunction "SCL/RX_19") (pintype "bidirectional"))
      (node (ref "U5") (pin "2") (pinfunction "SCL1_2") (pintype "bidirectional"))
    )
    (net (code "119") (name "SDA") (class "Default")
      (node (ref "R13") (pin "2") (pinfunction "2_2") (pintype "passive"))
      (node (ref "U1") (pin "27") (pinfunction "SDA_27") (pintype "bidirectional"))
      (node (ref "U2") (pin "27") (pinfunction "SDA_27") (pintype "bidirectional"))
      (node (ref "U5") (pin "5") (pinfunction "SDA2_5") (pintype "bidirectional"))
      (node (ref "U6") (pin "27") (pinfunction "SDA_27") (pintype "bidirectional"))
    )
    (net (code "120") (name "SDA33") (class "Default")
      (node (ref "TP1") (pin "TP") (pinfunction "TP_TP") (pintype "input"))
      (node (ref "U4") (pin "20") (pinfunction "SDA/TX_20") (pintype "bidirectional"))
      (node (ref "U5") (pin "3") (pinfunction "SDA1_3") (pintype "bidirectional"))
    )
    (net (code "121") (name "TERM") (class "Default")
      (node (ref "R12") (pin "1") (pinfunction "1_1") (pintype "passive"))
      (node (ref "R13") (pin "1") (pinfunction "1_1") (pintype "passive"))
      (node (ref "SW1") (pin "4") (pinfunction "4_4") (pintype "passive"))
    )
    (net (code "122") (name "VCC") (class "Default")
      (node (ref "C1") (pin "1") (pinfunction "1_1") (pintype "passive"))
      (node (ref "C15") (pin "1") (pinfunction "1_1") (pintype "passive"))
      (node (ref "C2") (pin "1") (pinfunction "1_1") (pintype "passive"))
      (node (ref "C25") (pin "1") (pinfunction "1_1") (pintype "passive"))
      (node (ref "C6") (pin "1") (pinfunction "1_1") (pintype "passive"))
      (node (ref "C7") (pin "1") (pinfunction "1_1") (pintype "passive"))
      (node (ref "Q1") (pin "2") (pinfunction "S_2") (pintype "passive"))
      (node (ref "R14") (pin "1") (pinfunction "1_1") (pintype "passive"))
      (node (ref "R15") (pin "2") (pinfunction "2_2") (pintype "passive"))
      (node (ref "R18") (pin "1") (pinfunction "1_1") (pintype "passive"))
      (node (ref "R21") (pin "2") (pinfunction "2_2") (pintype "passive"))
      (node (ref "R22") (pin "2") (pinfunction "2_2") (pintype "passive"))
      (node (ref "R33") (pin "2") (pinfunction "2_2") (pintype "passive"))
      (node (ref "S1") (pin "3") (pinfunction "2_3") (pintype "passive"))
      (node (ref "SW1") (pin "10") (pinfunction "10_10") (pintype "passive"))
      (node (ref "SW1") (pin "11") (pinfunction "11_11") (pintype "passive"))
      (node (ref "SW1") (pin "12") (pinfunction "12_12") (pintype "passive"))
      (node (ref "SW1") (pin "13") (pinfunction "13_13") (pintype "passive"))
      (node (ref "SW1") (pin "15") (pinfunction "15_15") (pintype "passive"))
      (node (ref "SW1") (pin "9") (pinfunction "9_9") (pintype "passive"))
      (node (ref "U1") (pin "28") (pinfunction "VDD_28") (pintype "power_in"))
      (node (ref "U11") (pin "1") (pinfunction "INPUT_1") (pintype "input"))
      (node (ref "U2") (pin "28") (pinfunction "VDD_28") (pintype "power_in"))
      (node (ref "U3") (pin "3") (pinfunction "VIN+_3") (pintype "bidirectional"))
      (node (ref "U3") (pin "5") (pinfunction "V+_5") (pintype "bidirectional"))
      (node (ref "U5") (pin "7") (pinfunction "VREF2_7") (pintype "bidirectional"))
    )
    (net (code "123") (name "VCCIO") (class "Default")
      (node (ref "C18") (pin "2") (pinfunction "2_2") (pintype "passive"))
      (node (ref "C21") (pin "2") (pinfunction "2_2") (pintype "passive"))
      (node (ref "C22") (pin "2") (pinfunction "2_2") (pintype "passive"))
      (node (ref "C24") (pin "2") (pinfunction "2_2") (pintype "passive"))
      (node (ref "C3") (pin "+") (pinfunction "+_+") (pintype "passive"))
      (node (ref "C5") (pin "+") (pinfunction "+_+") (pintype "passive"))
      (node (ref "JP2") (pin "1") (pinfunction "1_1") (pintype "passive"))
      (node (ref "JP2") (pin "10") (pinfunction "10_10") (pintype "passive"))
      (node (ref "JP2") (pin "11") (pinfunction "11_11") (pintype "passive"))
      (node (ref "JP2") (pin "12") (pinfunction "12_12") (pintype "passive"))
      (node (ref "JP2") (pin "13") (pinfunction "13_13") (pintype "passive"))
      (node (ref "JP2") (pin "14") (pinfunction "14_14") (pintype "passive"))
      (node (ref "JP2") (pin "15") (pinfunction "15_15") (pintype "passive"))
      (node (ref "JP2") (pin "16") (pinfunction "16_16") (pintype "passive"))
      (node (ref "JP2") (pin "2") (pinfunction "2_2") (pintype "passive"))
      (node (ref "JP2") (pin "3") (pinfunction "3_3") (pintype "passive"))
      (node (ref "JP2") (pin "4") (pinfunction "4_4") (pintype "passive"))
      (node (ref "JP2") (pin "5") (pinfunction "5_5") (pintype "passive"))
      (node (ref "JP2") (pin "6") (pinfunction "6_6") (pintype "passive"))
      (node (ref "JP2") (pin "7") (pinfunction "7_7") (pintype "passive"))
      (node (ref "JP2") (pin "8") (pinfunction "8_8") (pintype "passive"))
      (node (ref "JP2") (pin "9") (pinfunction "9_9") (pintype "passive"))
      (node (ref "JP6") (pin "1") (pinfunction "1_1") (pintype "passive"))
      (node (ref "JP6") (pin "10") (pinfunction "10_10") (pintype "passive"))
      (node (ref "JP6") (pin "11") (pinfunction "11_11") (pintype "passive"))
      (node (ref "JP6") (pin "12") (pinfunction "12_12") (pintype "passive"))
      (node (ref "JP6") (pin "13") (pinfunction "13_13") (pintype "passive"))
      (node (ref "JP6") (pin "14") (pinfunction "14_14") (pintype "passive"))
      (node (ref "JP6") (pin "15") (pinfunction "15_15") (pintype "passive"))
      (node (ref "JP6") (pin "16") (pinfunction "16_16") (pintype "passive"))
      (node (ref "JP6") (pin "2") (pinfunction "2_2") (pintype "passive"))
      (node (ref "JP6") (pin "3") (pinfunction "3_3") (pintype "passive"))
      (node (ref "JP6") (pin "4") (pinfunction "4_4") (pintype "passive"))
      (node (ref "JP6") (pin "5") (pinfunction "5_5") (pintype "passive"))
      (node (ref "JP6") (pin "6") (pinfunction "6_6") (pintype "passive"))
      (node (ref "JP6") (pin "7") (pinfunction "7_7") (pintype "passive"))
      (node (ref "JP6") (pin "8") (pinfunction "8_8") (pintype "passive"))
      (node (ref "JP6") (pin "9") (pinfunction "9_9") (pintype "passive"))
      (node (ref "Q1") (pin "3") (pinfunction "D_3") (pintype "passive"))
      (node (ref "R18") (pin "2") (pinfunction "2_2") (pintype "passive"))
      (node (ref "R23") (pin "2") (pinfunction "2_2") (pintype "passive"))
      (node (ref "U10") (pin "1") (pinfunction "VMOT_1") (pintype "bidirectional"))
      (node (ref "U3") (pin "4") (pinfunction "VIN-_4") (pintype "bidirectional"))
      (node (ref "U7") (pin "1") (pinfunction "VMOT_1") (pintype "bidirectional"))
      (node (ref "U8") (pin "1") (pinfunction "VMOT_1") (pintype "bidirectional"))
      (node (ref "U9") (pin "1") (pinfunction "VMOT_1") (pintype "bidirectional"))
    )
    (net (code "124") (name "VSENSE") (class "Default")
      (node (ref "C8") (pin "1") (pinfunction "1_1") (pintype "passive"))
      (node (ref "R15") (pin "1") (pinfunction "1_1") (pintype "passive"))
      (node (ref "R16") (pin "2") (pinfunction "2_2") (pintype "passive"))
    )
    (net (code "125") (name "unconnected-(U4-XIN-Pad27)") (class "Default")
      (node (ref "U4") (pin "27") (pinfunction "XIN_27") (pintype "bidirectional"))
    )
    (net (code "126") (name "unconnected-(U4-XOUT-Pad26)") (class "Default")
      (node (ref "U4") (pin "26") (pinfunction "XOUT_26") (pintype "bidirectional"))
    )
    (net (code "127") (name "~{BOOT}") (class "Default")
      (node (ref "R26") (pin "1") (pinfunction "1_1") (pintype "passive"))
      (node (ref "U4") (pin "4") (pinfunction "BOOT_4") (pintype "bidirectional"))
    )
    (net (code "128") (name "~{RST}") (class "Default")
      (node (ref "R27") (pin "1") (pinfunction "1_1") (pintype "passive"))
      (node (ref "U4") (pin "1") (pinfunction "RST_1") (pintype "bidirectional"))
    )
  )
)
